# SOIC16-TSSOP16.net
KiCad netlist of a schematic drawn in EAGLE
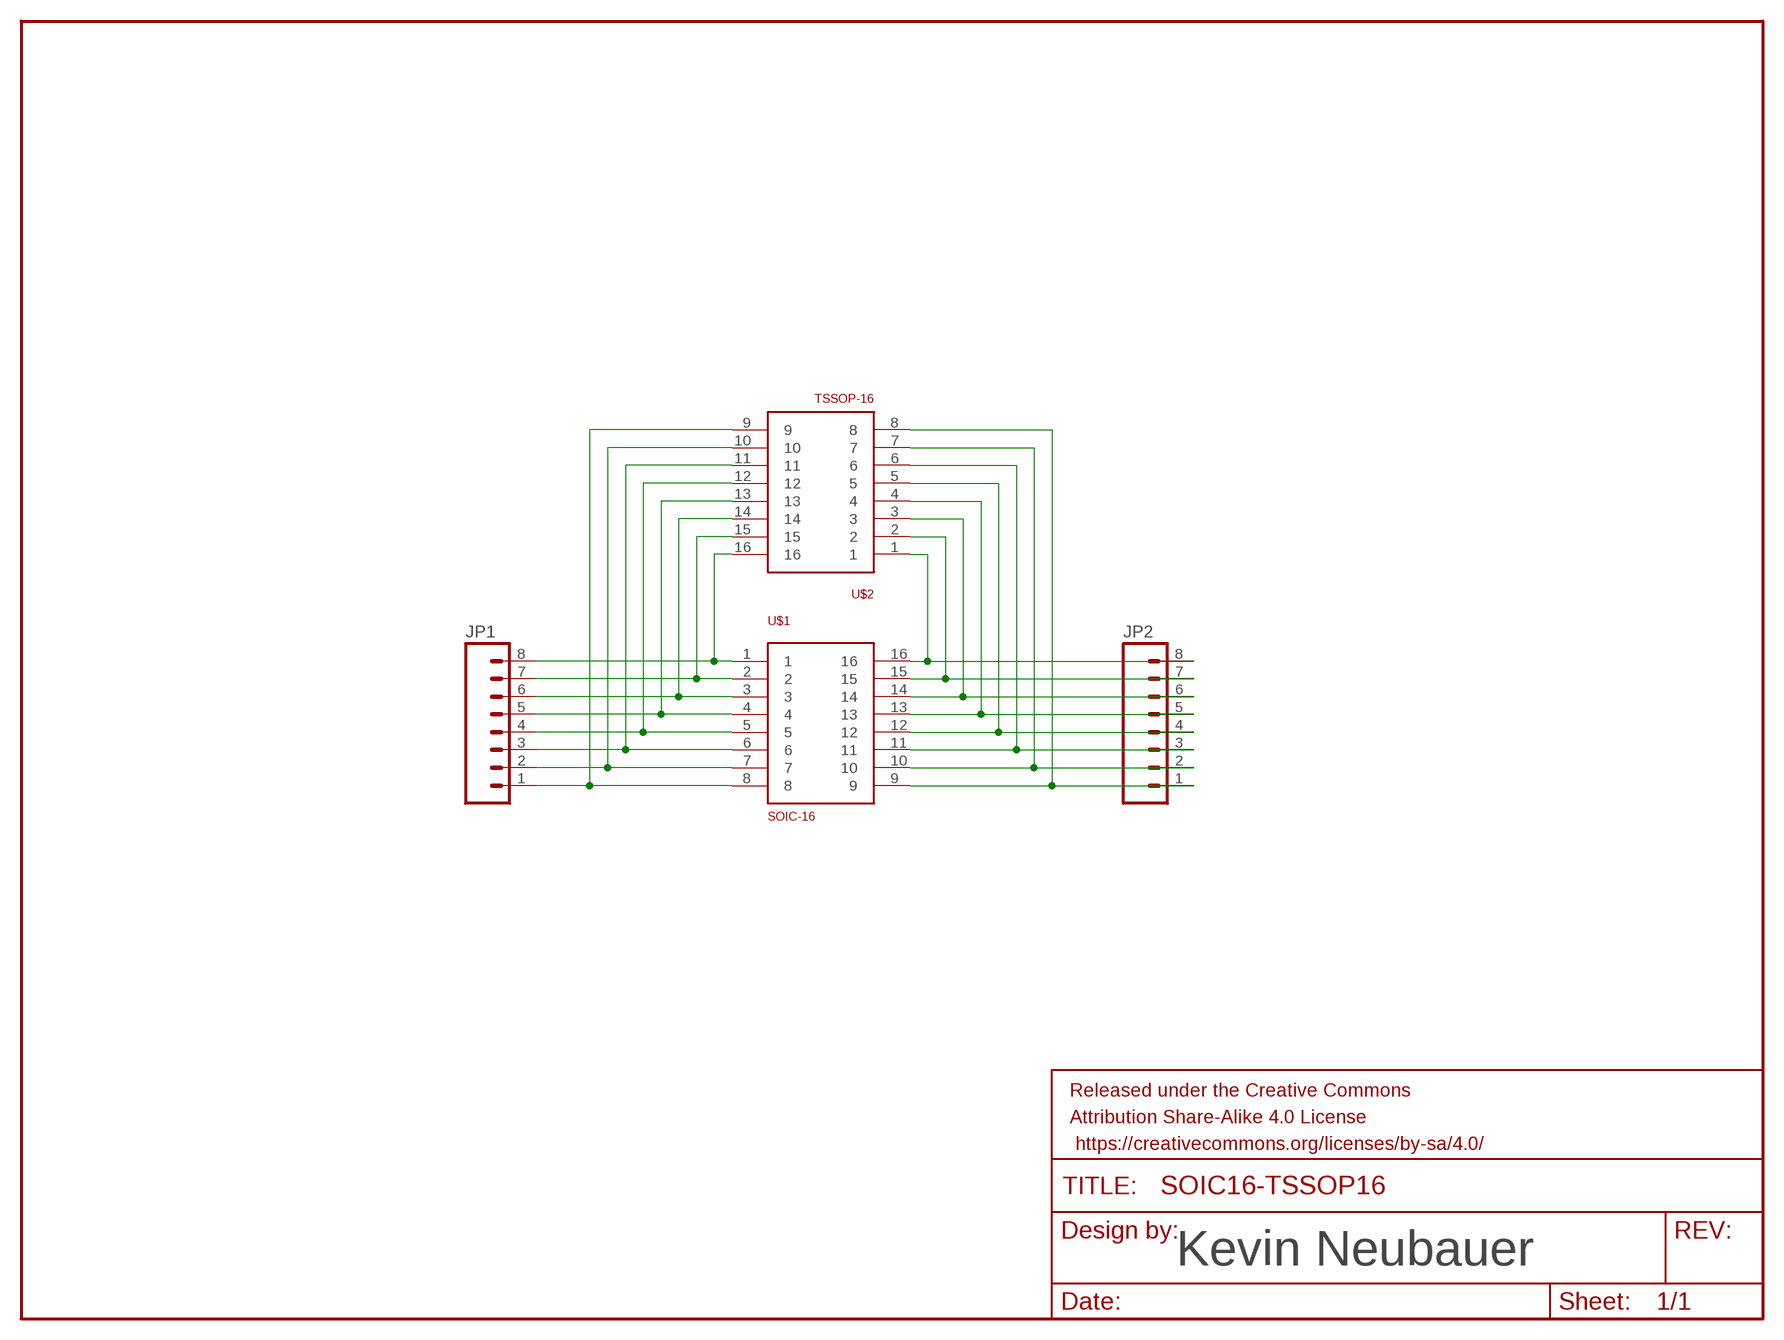
[diagram p0: schematic, sheet 1]

(export (version "E")
  (design (tool "Eeschema 10.0.6"))
  (components
    (comp (ref "FRAME1")
      (value "FRAME-LETTER")
      (footprint "eagle-import:CREATIVE_COMMONS")
      (libsource (lib "eagle-import") (part "FRAME-LETTER"))
    )
    (comp (ref "JP1")
      (value "M08NO_SILK")
      (footprint "eagle-import:1X08_NO_SILK")
      (libsource (lib "eagle-import") (part "M08NO_SILK"))
    )
    (comp (ref "JP2")
      (value "M08NO_SILK")
      (footprint "eagle-import:1X08_NO_SILK")
      (libsource (lib "eagle-import") (part "M08NO_SILK"))
    )
    (comp (ref "U$1")
      (value "SOIC-16")
      (footprint "eagle-import:SO16")
      (libsource (lib "eagle-import") (part "SOIC-16"))
    )
    (comp (ref "U$2")
      (value "TSSOP-16")
      (footprint "eagle-import:TSSOP16")
      (libsource (lib "eagle-import") (part "TSSOP-16"))
    )
  )
  (nets
    (net (code "1") (name "Net-(JP1-Pad1)") (class "Default")
      (node (ref "JP1") (pin "1") (pinfunction "1_1") (pintype "passive"))
      (node (ref "U$1") (pin "8") (pinfunction "8_8") (pintype "bidirectional"))
      (node (ref "U$2") (pin "9") (pinfunction "9_9") (pintype "bidirectional"))
    )
    (net (code "2") (name "Net-(JP1-Pad2)") (class "Default")
      (node (ref "JP1") (pin "2") (pinfunction "2_2") (pintype "passive"))
      (node (ref "U$1") (pin "7") (pinfunction "7_7") (pintype "bidirectional"))
      (node (ref "U$2") (pin "10") (pinfunction "10_10") (pintype "bidirectional"))
    )
    (net (code "3") (name "Net-(JP1-Pad3)") (class "Default")
      (node (ref "JP1") (pin "3") (pinfunction "3_3") (pintype "passive"))
      (node (ref "U$1") (pin "6") (pinfunction "6_6") (pintype "bidirectional"))
      (node (ref "U$2") (pin "11") (pinfunction "11_11") (pintype "bidirectional"))
    )
    (net (code "4") (name "Net-(JP1-Pad4)") (class "Default")
      (node (ref "JP1") (pin "4") (pinfunction "4_4") (pintype "passive"))
      (node (ref "U$1") (pin "5") (pinfunction "5_5") (pintype "bidirectional"))
      (node (ref "U$2") (pin "12") (pinfunction "12_12") (pintype "bidirectional"))
    )
    (net (code "5") (name "Net-(JP1-Pad5)") (class "Default")
      (node (ref "JP1") (pin "5") (pinfunction "5_5") (pintype "passive"))
      (node (ref "U$1") (pin "4") (pinfunction "4_4") (pintype "bidirectional"))
      (node (ref "U$2") (pin "13") (pinfunction "13_13") (pintype "bidirectional"))
    )
    (net (code "6") (name "Net-(JP1-Pad6)") (class "Default")
      (node (ref "JP1") (pin "6") (pinfunction "6_6") (pintype "passive"))
      (node (ref "U$1") (pin "3") (pinfunction "3_3") (pintype "bidirectional"))
      (node (ref "U$2") (pin "14") (pinfunction "14_14") (pintype "bidirectional"))
    )
    (net (code "7") (name "Net-(JP1-Pad7)") (class "Default")
      (node (ref "JP1") (pin "7") (pinfunction "7_7") (pintype "passive"))
      (node (ref "U$1") (pin "2") (pinfunction "2_2") (pintype "bidirectional"))
      (node (ref "U$2") (pin "15") (pinfunction "15_15") (pintype "bidirectional"))
    )
    (net (code "8") (name "Net-(JP1-Pad8)") (class "Default")
      (node (ref "JP1") (pin "8") (pinfunction "8_8") (pintype "passive"))
      (node (ref "U$1") (pin "1") (pinfunction "1_1") (pintype "bidirectional"))
      (node (ref "U$2") (pin "16") (pinfunction "16_16") (pintype "bidirectional"))
    )
    (net (code "9") (name "Net-(JP2-Pad1)") (class "Default")
      (node (ref "JP2") (pin "1") (pinfunction "1_1") (pintype "passive"))
      (node (ref "U$1") (pin "9") (pinfunction "9_9") (pintype "bidirectional"))
      (node (ref "U$2") (pin "8") (pinfunction "8_8") (pintype "bidirectional"))
    )
    (net (code "10") (name "Net-(JP2-Pad2)") (class "Default")
      (node (ref "JP2") (pin "2") (pinfunction "2_2") (pintype "passive"))
      (node (ref "U$1") (pin "10") (pinfunction "10_10") (pintype "bidirectional"))
      (node (ref "U$2") (pin "7") (pinfunction "7_7") (pintype "bidirectional"))
    )
    (net (code "11") (name "Net-(JP2-Pad3)") (class "Default")
      (node (ref "JP2") (pin "3") (pinfunction "3_3") (pintype "passive"))
      (node (ref "U$1") (pin "11") (pinfunction "11_11") (pintype "bidirectional"))
      (node (ref "U$2") (pin "6") (pinfunction "6_6") (pintype "bidirectional"))
    )
    (net (code "12") (name "Net-(JP2-Pad4)") (class "Default")
      (node (ref "JP2") (pin "4") (pinfunction "4_4") (pintype "passive"))
      (node (ref "U$1") (pin "12") (pinfunction "12_12") (pintype "bidirectional"))
      (node (ref "U$2") (pin "5") (pinfunction "5_5") (pintype "bidirectional"))
    )
    (net (code "13") (name "Net-(JP2-Pad5)") (class "Default")
      (node (ref "JP2") (pin "5") (pinfunction "5_5") (pintype "passive"))
      (node (ref "U$1") (pin "13") (pinfunction "13_13") (pintype "bidirectional"))
      (node (ref "U$2") (pin "4") (pinfunction "4_4") (pintype "bidirectional"))
    )
    (net (code "14") (name "Net-(JP2-Pad6)") (class "Default")
      (node (ref "JP2") (pin "6") (pinfunction "6_6") (pintype "passive"))
      (node (ref "U$1") (pin "14") (pinfunction "14_14") (pintype "bidirectional"))
      (node (ref "U$2") (pin "3") (pinfunction "3_3") (pintype "bidirectional"))
    )
    (net (code "15") (name "Net-(JP2-Pad7)") (class "Default")
      (node (ref "JP2") (pin "7") (pinfunction "7_7") (pintype "passive"))
      (node (ref "U$1") (pin "15") (pinfunction "15_15") (pintype "bidirectional"))
      (node (ref "U$2") (pin "2") (pinfunction "2_2") (pintype "bidirectional"))
    )
    (net (code "16") (name "Net-(JP2-Pad8)") (class "Default")
      (node (ref "JP2") (pin "8") (pinfunction "8_8") (pintype "passive"))
      (node (ref "U$1") (pin "16") (pinfunction "16_16") (pintype "bidirectional"))
      (node (ref "U$2") (pin "1") (pinfunction "1_1") (pintype "bidirectional"))
    )
  )
)
